# AAI.net
KiCad netlist of a schematic drawn in Altium Designer
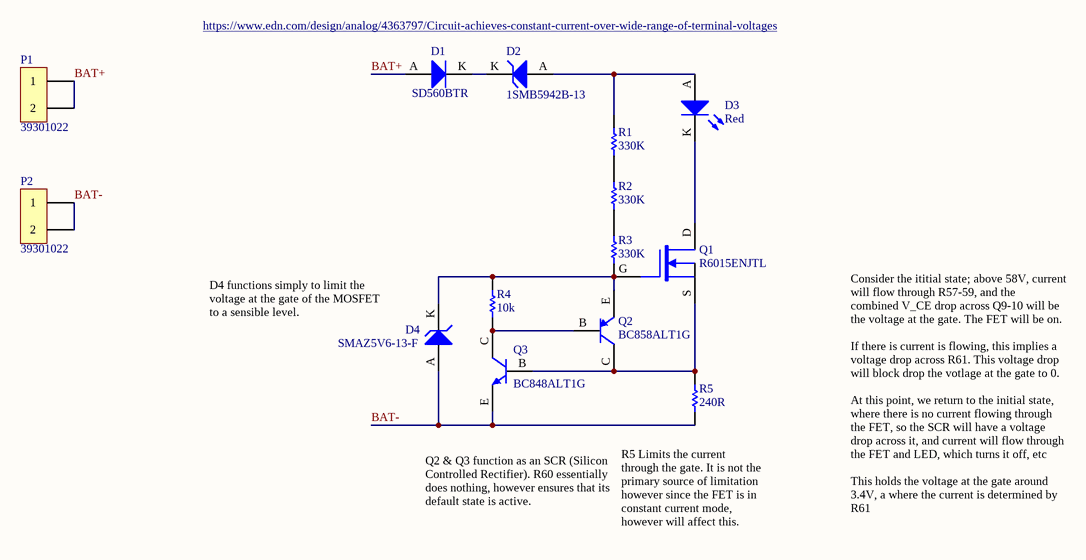
[diagram p0: AAI.SchDoc]

(export (version "E")
  (design (tool "Eeschema 10.0.6"))
  (components
    (comp (ref "D1")
      (value "SD560BTR")
      (footprint "SMB Diode")
      (description "1.2V_F 600V 5A SMB")
      (fields
        (field (name "MANUFACTURER") "SMC Diode Solutions")
        (field (name "DIGIKEY PART NUMBER") "1655-1530-2-ND")
      )
      (libsource (lib "ts_20-standard-library") (part "Diode"))
    )
    (comp (ref "D2")
      (value "1SMB5942B-13")
      (footprint "DI SMB Diode")
      (description "DIODE ZENER 51V 3W SMB")
      (fields
        (field (name "MANUFACTURER") "Diodes Inc")
        (field (name "DIGIKEY PART NUMBER") "1SMB5942B-13DICT-ND")
      )
      (libsource (lib "ts_20-standard-library") (part "Zener Diode"))
    )
    (comp (ref "D3")
      (value "Red")
      (footprint "0805 LED")
      (description "Red LED Indication - Discrete 1.75V 0805 (2012 Metric)")
      (fields (field (name "PART NUMBER") "SML-210LTT86") (field (name "MANUFACTURER") "ROHM Semiconductor"))
      (libsource (lib "ts_20-standard-library") (part "LED"))
    )
    (comp (ref "D4")
      (value "SMAZ5V6-13-F")
      (footprint "DI SMA Diode")
      (description "DIODE ZENER 5.6V 1W SMA")
      (fields
        (field (name "MANUFACTURER") "Diodes Inc")
        (field (name "DIGIKEY PART NUMBER") "SMAZ5V6-FDICT-ND")
      )
      (libsource (lib "ts_20-standard-library") (part "Zener Diode"))
    )
    (comp (ref "P1")
      (value "39301022")
      (footprint "39301022")
      (fields (field (name "DIGIKEY PART NUMBER") "WM21363-ND") (field (name "CONTACT") "Gold"))
      (libsource (lib "ts_19-standard-connectors") (part "39301022"))
    )
    (comp (ref "P2")
      (value "39301022")
      (footprint "39301022")
      (fields (field (name "DIGIKEY PART NUMBER") "WM21363-ND") (field (name "CONTACT") "Gold"))
      (libsource (lib "ts_20-standard-connectors") (part "39301022"))
    )
    (comp (ref "Q1")
      (value "R6015ENJTL")
      (footprint "R TO-263 N-MOSFET")
      (description "MOSFET N-CH 600V 15A LPT")
      (fields
        (field (name "MANUFACTURER") "Rohm Semiconductor")
        (field (name "DIGIKEY PART NUMBER") "R6015ENJTLCT-ND")
        (field (name "PUBLISHER") "Altium Limited")
      )
      (libsource (lib "ts_20-standard-library") (part "MOSFET-N"))
    )
    (comp (ref "Q2")
      (value "BC858ALT1G")
      (footprint "ON TO-236-3 BJT")
      (description "TRANS PNP 30V 0.1A SOT-23")
      (fields
        (field (name "MANUFACTURER") "ON Semiconductor")
        (field (name "DIGIKEY PART NUMBER") "BC858ALT1GOSCT-ND")
      )
      (libsource (lib "ts_20-standard-library") (part "PNP"))
    )
    (comp (ref "Q3")
      (value "BC848ALT1G")
      (footprint "ON TO-236-3 BJT")
      (description "TRANS NPN 30V 0.1A SOT23")
      (fields
        (field (name "MANUFACTURER") "ON Semiconductor")
        (field (name "DIGIKEY PART NUMBER") "BC848ALT1GOSCT-ND")
      )
      (libsource (lib "ts_20-standard-library") (part "NPN"))
    )
    (comp (ref "R1")
      (value "330K")
      (footprint "VB 0207")
      (fields
        (field (name "PART NUMBER") "MMB02070C3303FB200")
        (field (name "MANUFACTURER") "Vishay Beyschlag")
        (field (name "TOLERANCE") "0.01")
      )
      (libsource (lib "ts_20-standard-library") (part "Resistor"))
    )
    (comp (ref "R2")
      (value "330K")
      (footprint "VB 0207")
      (fields
        (field (name "PART NUMBER") "MMB02070C3303FB200")
        (field (name "MANUFACTURER") "Vishay Beyschlag")
        (field (name "TOLERANCE") "0.01")
      )
      (libsource (lib "ts_20-standard-library") (part "Resistor"))
    )
    (comp (ref "R3")
      (value "330K")
      (footprint "VB 0207")
      (fields
        (field (name "PART NUMBER") "MMB02070C3303FB200")
        (field (name "MANUFACTURER") "Vishay Beyschlag")
        (field (name "TOLERANCE") "0.01")
      )
      (libsource (lib "ts_20-standard-library") (part "Resistor"))
    )
    (comp (ref "R4")
      (value "10k")
      (footprint "0805")
      (fields
        (field (name "PART NUMBER") "RC0805FR0710KL")
        (field (name "MANUFACTURER") "YAGEO")
        (field (name "TOLERANCE") "0.01")
      )
      (libsource (lib "ts_20-standard-library") (part "Resistor"))
    )
    (comp (ref "R5")
      (value "240R")
      (footprint "0805")
      (fields
        (field (name "PART NUMBER") "RC0805FR07240RL")
        (field (name "MANUFACTURER") "YAGEO")
        (field (name "TOLERANCE") "0.01")
      )
      (libsource (lib "ts_20-standard-library") (part "Resistor"))
    )
  )
  (nets
    (net (code "2") (name "/BAT+") (class "Default")
      (node (ref "D1") (pin "A") (pinfunction "A_A") (pintype "passive"))
      (node (ref "P1") (pin "1") (pinfunction "1_1") (pintype "passive"))
      (node (ref "P1") (pin "2") (pinfunction "2_2") (pintype "passive"))
    )
    (net (code "3") (name "/BAT-") (class "Default")
      (node (ref "D4") (pin "A") (pinfunction "A_A") (pintype "passive"))
      (node (ref "P2") (pin "1") (pinfunction "1_1") (pintype "passive"))
      (node (ref "P2") (pin "2") (pinfunction "2_2") (pintype "passive"))
      (node (ref "Q3") (pin "E") (pinfunction "E_E") (pintype "passive"))
      (node (ref "R5") (pin "1") (pinfunction "1_1") (pintype "passive"))
    )
    (net (code "4") (name "Net-(D1-PadK)") (class "Default")
      (node (ref "D1") (pin "K") (pinfunction "K_K") (pintype "passive"))
      (node (ref "D2") (pin "K") (pinfunction "K_K") (pintype "passive"))
    )
    (net (code "5") (name "Net-(D2-PadA)") (class "Default")
      (node (ref "D2") (pin "A") (pinfunction "A_A") (pintype "passive"))
      (node (ref "D3") (pin "A") (pinfunction "A_A") (pintype "passive"))
      (node (ref "R1") (pin "2") (pinfunction "2_2") (pintype "passive"))
    )
    (net (code "6") (name "Net-(D3-PadK)") (class "Default")
      (node (ref "D3") (pin "K") (pinfunction "K_K") (pintype "passive"))
      (node (ref "Q1") (pin "D") (pinfunction "D_D") (pintype "passive"))
    )
    (net (code "7") (name "Net-(D4-PadK)") (class "Default")
      (node (ref "D4") (pin "K") (pinfunction "K_K") (pintype "passive"))
      (node (ref "Q1") (pin "G") (pinfunction "G_G") (pintype "passive"))
      (node (ref "Q2") (pin "E") (pinfunction "E_E") (pintype "passive"))
      (node (ref "R3") (pin "1") (pinfunction "1_1") (pintype "passive"))
      (node (ref "R4") (pin "2") (pinfunction "2_2") (pintype "passive"))
    )
    (net (code "8") (name "Net-(Q1-PadS)") (class "Default")
      (node (ref "Q1") (pin "S") (pinfunction "S_S") (pintype "passive"))
      (node (ref "Q2") (pin "C") (pinfunction "C_C") (pintype "passive"))
      (node (ref "Q3") (pin "B") (pinfunction "B_B") (pintype "passive"))
      (node (ref "R5") (pin "2") (pinfunction "2_2") (pintype "passive"))
    )
    (net (code "9") (name "Net-(Q2-PadB)") (class "Default")
      (node (ref "Q2") (pin "B") (pinfunction "B_B") (pintype "passive"))
      (node (ref "Q3") (pin "C") (pinfunction "C_C") (pintype "passive"))
      (node (ref "R4") (pin "1") (pinfunction "1_1") (pintype "passive"))
    )
    (net (code "10") (name "Net-(R1-Pad1)") (class "Default")
      (node (ref "R1") (pin "1") (pinfunction "1_1") (pintype "passive"))
      (node (ref "R2") (pin "2") (pinfunction "2_2") (pintype "passive"))
    )
    (net (code "11") (name "Net-(R2-Pad1)") (class "Default")
      (node (ref "R2") (pin "1") (pinfunction "1_1") (pintype "passive"))
      (node (ref "R3") (pin "2") (pinfunction "2_2") (pintype "passive"))
    )
  )
)
